# control_board.net
KiCad netlist of a schematic drawn in EAGLE
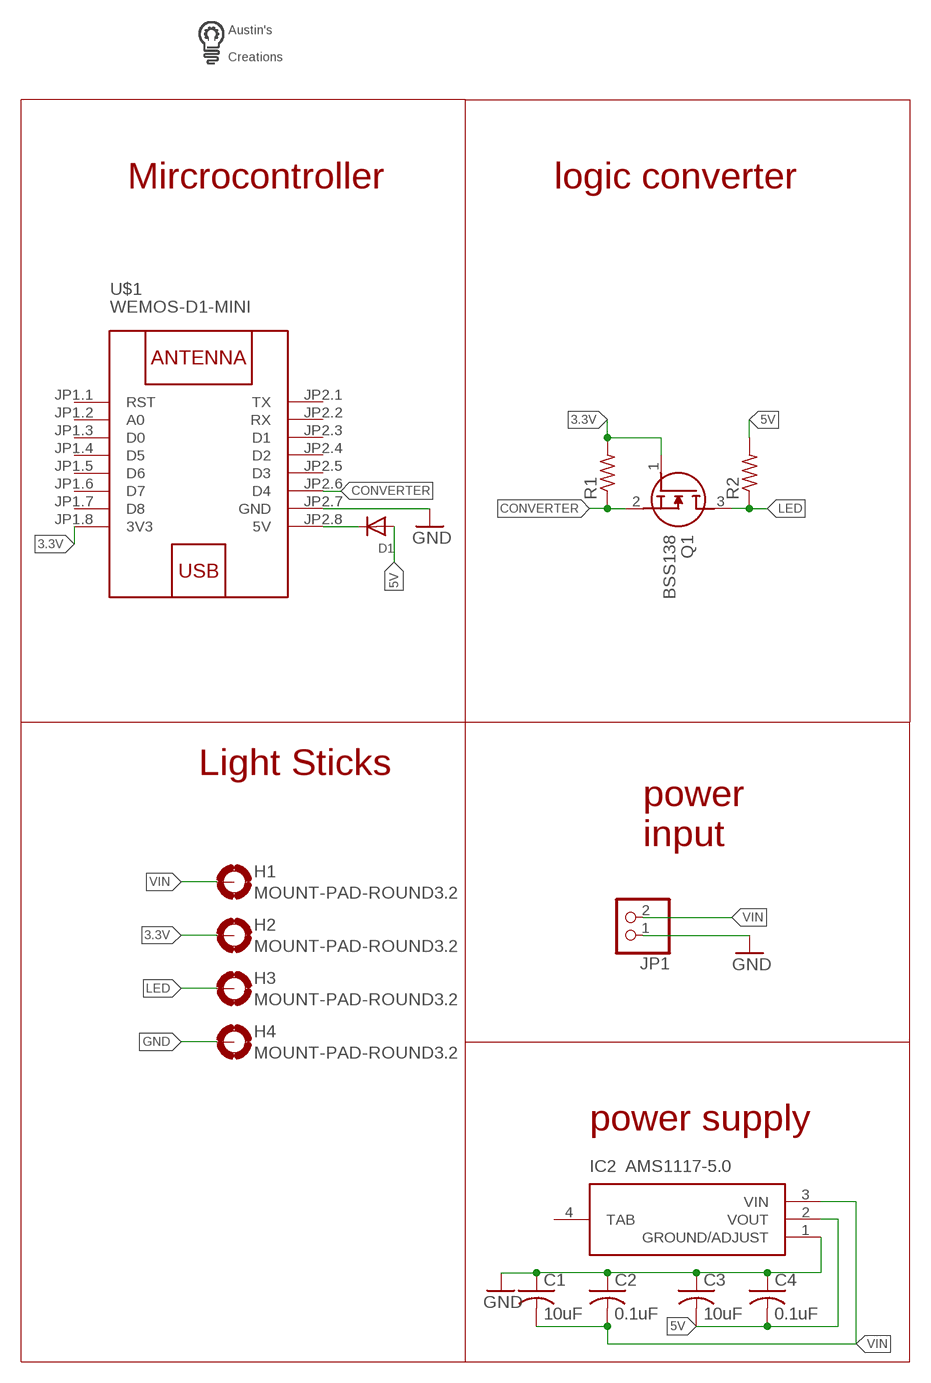
[diagram p0: schematic, sheet 1]

(export (version "E")
  (design (tool "Eeschema 10.0.6"))
  (components
    (comp (ref "C1")
      (value "10uF")
      (footprint "eagle-import:C0603")
      (libsource (lib "eagle-import") (part "C-USC0603"))
    )
    (comp (ref "C2")
      (value "0.1uF")
      (footprint "eagle-import:C0603")
      (libsource (lib "eagle-import") (part "C-USC0603"))
    )
    (comp (ref "C3")
      (value "10uF")
      (footprint "eagle-import:C0603")
      (libsource (lib "eagle-import") (part "C-USC0603"))
    )
    (comp (ref "C4")
      (value "0.1uF")
      (footprint "eagle-import:C0603")
      (libsource (lib "eagle-import") (part "C-USC0603"))
    )
    (comp (ref "D1")
      (value "DIODESOD-123")
      (footprint "eagle-import:SOD-123")
      (libsource (lib "eagle-import") (part "DIODESOD-123"))
    )
    (comp (ref "H1")
      (value "MOUNT-PAD-ROUND3.2")
      (footprint "eagle-import:3,2-PAD")
      (libsource (lib "eagle-import") (part "MOUNT-PAD-ROUND3.2"))
    )
    (comp (ref "H2")
      (value "MOUNT-PAD-ROUND3.2")
      (footprint "eagle-import:3,2-PAD")
      (libsource (lib "eagle-import") (part "MOUNT-PAD-ROUND3.2"))
    )
    (comp (ref "H3")
      (value "MOUNT-PAD-ROUND3.2")
      (footprint "eagle-import:3,2-PAD")
      (libsource (lib "eagle-import") (part "MOUNT-PAD-ROUND3.2"))
    )
    (comp (ref "H4")
      (value "MOUNT-PAD-ROUND3.2")
      (footprint "eagle-import:3,2-PAD")
      (libsource (lib "eagle-import") (part "MOUNT-PAD-ROUND3.2"))
    )
    (comp (ref "IC2")
      (value "AMS1117-5.0")
      (footprint "eagle-import:SOT229P700X180-4N")
      (libsource (lib "eagle-import") (part "AMS1117-5.0"))
    )
    (comp (ref "JP1")
      (value "PINHD-1X2")
      (footprint "eagle-import:1X02")
      (libsource (lib "eagle-import") (part "PINHD-1X2"))
    )
    (comp (ref "Q1")
      (value "BSS138")
      (footprint "eagle-import:SOT95P240X120-3N")
      (fields (field (name "MOUSER_PART_NUMBER") "512-BSS138"))
      (libsource (lib "eagle-import") (part "BSS138"))
    )
    (comp (ref "R1")
      (value "R-US_R0603")
      (footprint "eagle-import:R0603")
      (libsource (lib "eagle-import") (part "R-US_R0603"))
    )
    (comp (ref "R2")
      (value "R-US_R0603")
      (footprint "eagle-import:R0603")
      (libsource (lib "eagle-import") (part "R-US_R0603"))
    )
    (comp (ref "U$1")
      (value "WEMOS-D1-MINI")
      (footprint "eagle-import:WEMOS-D1-MINI")
      (libsource (lib "eagle-import") (part "WEMOS-D1-MINI"))
    )
    (comp (ref "U$2")
      (value "LOGO")
      (footprint "eagle-import:LOGO")
      (libsource (lib "eagle-import") (part "LOGO"))
    )
  )
  (nets
    (net (code "1") (name "3.3V") (class "Default")
      (node (ref "H2") (pin "B3,2") (pinfunction "MOUNT_B3,2") (pintype "passive"))
      (node (ref "Q1") (pin "1") (pinfunction "G_1") (pintype "bidirectional"))
      (node (ref "R1") (pin "2") (pinfunction "2_2") (pintype "passive"))
      (node (ref "U$1") (pin "JP1.8") (pinfunction "3V3_JP1.8") (pintype "power_in"))
    )
    (net (code "2") (name "5V") (class "Default")
      (node (ref "C3") (pin "2") (pinfunction "2_2") (pintype "passive"))
      (node (ref "C4") (pin "2") (pinfunction "2_2") (pintype "passive"))
      (node (ref "D1") (pin "A") (pinfunction "A_A") (pintype "passive"))
      (node (ref "IC2") (pin "2") (pinfunction "VOUT_2") (pintype "bidirectional"))
      (node (ref "R2") (pin "2") (pinfunction "2_2") (pintype "passive"))
    )
    (net (code "3") (name "CONVERTER") (class "Default")
      (node (ref "Q1") (pin "2") (pinfunction "S_2") (pintype "bidirectional"))
      (node (ref "R1") (pin "1") (pinfunction "1_1") (pintype "passive"))
      (node (ref "U$1") (pin "JP2.6") (pinfunction "D4_JP2.6") (pintype "bidirectional"))
    )
    (net (code "4") (name "GND") (class "Default")
      (node (ref "C1") (pin "1") (pinfunction "1_1") (pintype "passive"))
      (node (ref "C2") (pin "1") (pinfunction "1_1") (pintype "passive"))
      (node (ref "C3") (pin "1") (pinfunction "1_1") (pintype "passive"))
      (node (ref "C4") (pin "1") (pinfunction "1_1") (pintype "passive"))
      (node (ref "H4") (pin "B3,2") (pinfunction "MOUNT_B3,2") (pintype "passive"))
      (node (ref "IC2") (pin "1") (pinfunction "GROUND/ADJUST_1") (pintype "bidirectional"))
      (node (ref "JP1") (pin "1") (pinfunction "1_1") (pintype "passive"))
      (node (ref "U$1") (pin "JP2.7") (pinfunction "GND_JP2.7") (pintype "power_in"))
    )
    (net (code "5") (name "LED") (class "Default")
      (node (ref "H3") (pin "B3,2") (pinfunction "MOUNT_B3,2") (pintype "passive"))
      (node (ref "Q1") (pin "3") (pinfunction "D_3") (pintype "bidirectional"))
      (node (ref "R2") (pin "1") (pinfunction "1_1") (pintype "passive"))
    )
    (net (code "6") (name "Net-(U$1-5V)") (class "Default")
      (node (ref "D1") (pin "C") (pinfunction "C_C") (pintype "passive"))
      (node (ref "U$1") (pin "JP2.8") (pinfunction "5V_JP2.8") (pintype "power_in"))
    )
    (net (code "7") (name "VIN") (class "Default")
      (node (ref "C1") (pin "2") (pinfunction "2_2") (pintype "passive"))
      (node (ref "C2") (pin "2") (pinfunction "2_2") (pintype "passive"))
      (node (ref "H1") (pin "B3,2") (pinfunction "MOUNT_B3,2") (pintype "passive"))
      (node (ref "IC2") (pin "3") (pinfunction "VIN_3") (pintype "bidirectional"))
      (node (ref "JP1") (pin "2") (pinfunction "2_2") (pintype "passive"))
    )
    (net (code "8") (name "unconnected-(IC2-TAB-Pad4)") (class "Default")
      (node (ref "IC2") (pin "4") (pinfunction "TAB_4") (pintype "bidirectional"))
    )
    (net (code "9") (name "unconnected-(U$1-A0-PadJP1.2)") (class "Default")
      (node (ref "U$1") (pin "JP1.2") (pinfunction "A0_JP1.2") (pintype "bidirectional"))
    )
    (net (code "10") (name "unconnected-(U$1-D0-PadJP1.3)") (class "Default")
      (node (ref "U$1") (pin "JP1.3") (pinfunction "D0_JP1.3") (pintype "bidirectional"))
    )
    (net (code "11") (name "unconnected-(U$1-D1-PadJP2.3)") (class "Default")
      (node (ref "U$1") (pin "JP2.3") (pinfunction "D1_JP2.3") (pintype "bidirectional"))
    )
    (net (code "12") (name "unconnected-(U$1-D2-PadJP2.4)") (class "Default")
      (node (ref "U$1") (pin "JP2.4") (pinfunction "D2_JP2.4") (pintype "bidirectional"))
    )
    (net (code "13") (name "unconnected-(U$1-D3-PadJP2.5)") (class "Default")
      (node (ref "U$1") (pin "JP2.5") (pinfunction "D3_JP2.5") (pintype "bidirectional"))
    )
    (net (code "14") (name "unconnected-(U$1-D5-PadJP1.4)") (class "Default")
      (node (ref "U$1") (pin "JP1.4") (pinfunction "D5_JP1.4") (pintype "bidirectional"))
    )
    (net (code "15") (name "unconnected-(U$1-D6-PadJP1.5)") (class "Default")
      (node (ref "U$1") (pin "JP1.5") (pinfunction "D6_JP1.5") (pintype "bidirectional"))
    )
    (net (code "16") (name "unconnected-(U$1-D7-PadJP1.6)") (class "Default")
      (node (ref "U$1") (pin "JP1.6") (pinfunction "D7_JP1.6") (pintype "bidirectional"))
    )
    (net (code "17") (name "unconnected-(U$1-D8-PadJP1.7)") (class "Default")
      (node (ref "U$1") (pin "JP1.7") (pinfunction "D8_JP1.7") (pintype "bidirectional"))
    )
    (net (code "18") (name "unconnected-(U$1-RST-PadJP1.1)") (class "Default")
      (node (ref "U$1") (pin "JP1.1") (pinfunction "RST_JP1.1") (pintype "bidirectional"))
    )
    (net (code "19") (name "unconnected-(U$1-RX-PadJP2.2)") (class "Default")
      (node (ref "U$1") (pin "JP2.2") (pinfunction "RX_JP2.2") (pintype "bidirectional"))
    )
    (net (code "20") (name "unconnected-(U$1-TX-PadJP2.1)") (class "Default")
      (node (ref "U$1") (pin "JP2.1") (pinfunction "TX_JP2.1") (pintype "bidirectional"))
    )
  )
)
